# RFLNA.net
KiCad netlist of a schematic drawn in Altium Designer
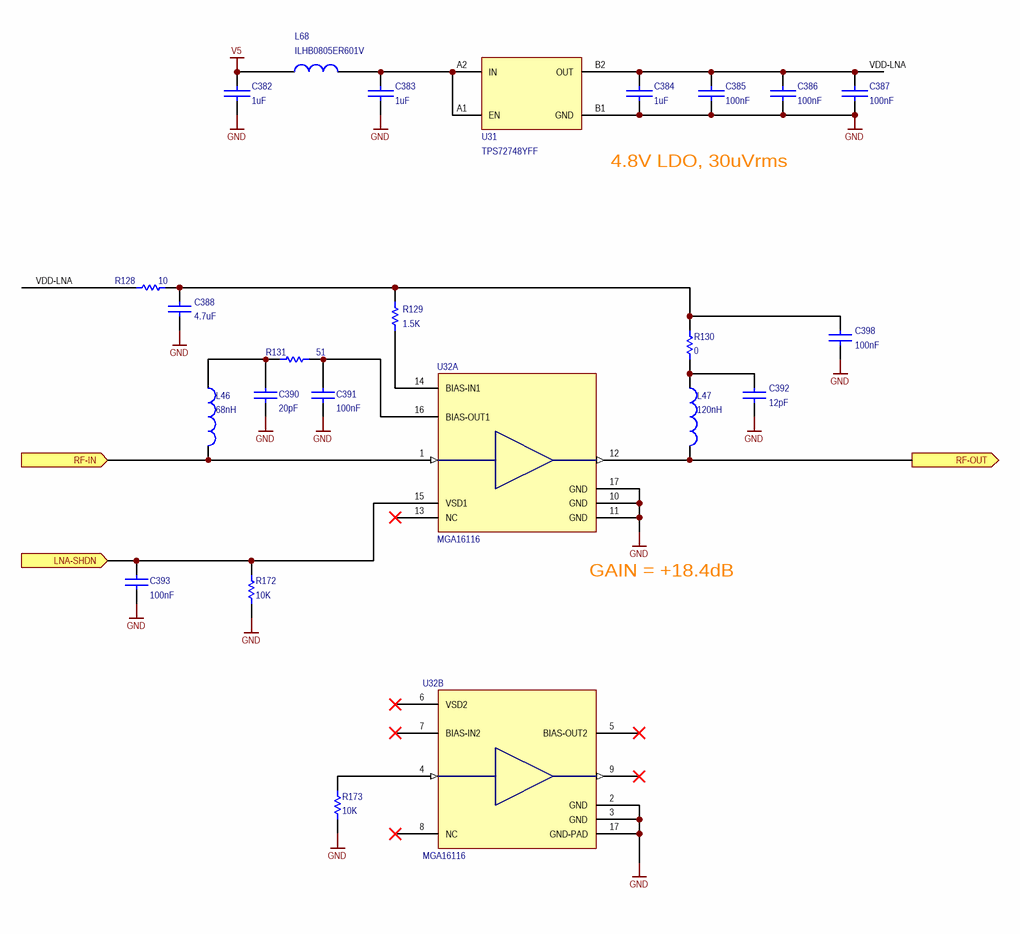
[diagram p0: RFLNA.SchDoc]

(export (version "E")
  (design (tool "Eeschema 10.0.6"))
  (components
    (comp (ref "C382")
      (value "1uF")
      (footprint "generic:0402")
      (description "Ceramic Capacitor 1uF ±10% 10V X5R 0402")
      (fields (field (name "MANUFACTURER") "Murata") (field (name "TOLERANCE") "±10%"))
      (libsource (lib "*") (part "CAP"))
    )
    (comp (ref "C383")
      (value "1uF")
      (footprint "generic:0402")
      (description "Ceramic Capacitor 1uF ±10% 10V X5R 0402")
      (fields (field (name "MANUFACTURER") "Murata") (field (name "TOLERANCE") "±10%"))
      (libsource (lib "*") (part "CAP"))
    )
    (comp (ref "C384")
      (value "1uF")
      (footprint "generic:0402")
      (description "Ceramic Capacitor 1uF ±10% 10V X5R 0402")
      (fields (field (name "MANUFACTURER") "Murata") (field (name "TOLERANCE") "±10%"))
      (libsource (lib "*") (part "CAP"))
    )
    (comp (ref "C385")
      (value "100nF")
      (footprint "generic:0402")
      (description "Ceramic Capacitor 100nF ±10% 16V X7R 0402")
      (fields (field (name "MANUFACTURER") "Murata") (field (name "VOLTAGE") "16V"))
      (libsource (lib "*") (part "CAP"))
    )
    (comp (ref "C386")
      (value "100nF")
      (footprint "generic:0402")
      (description "Ceramic Capacitor 100nF ±10% 16V X7R 0402")
      (fields (field (name "MANUFACTURER") "Murata") (field (name "VOLTAGE") "16V"))
      (libsource (lib "*") (part "CAP"))
    )
    (comp (ref "C387")
      (value "100nF")
      (footprint "generic:0402")
      (description "Ceramic Capacitor 100nF ±10% 16V X7R 0402")
      (fields (field (name "MANUFACTURER") "Murata") (field (name "VOLTAGE") "16V"))
      (libsource (lib "*") (part "CAP"))
    )
    (comp (ref "C388")
      (value "4.7uF")
      (footprint "generic:0603")
      (description "Ceramic Capacitor 4.7uF ±10% 25V X5R 0603")
      (fields (field (name "VOLTAGE") "25V") (field (name "MANUFACTURER") "Samsung"))
      (libsource (lib "Graviton") (part "CAP 0603"))
    )
    (comp (ref "C390")
      (value "20pF")
      (footprint "generic:0402")
      (description "Ceramic Capacitor 20pF ±1% 50V NP0 0402")
      (fields (field (name "VOLTAGE") "50V") (field (name "MANUFACTURER") "Kemet"))
      (libsource (lib "PopRock") (part "CAP 0402"))
    )
    (comp (ref "C391")
      (value "100nF")
      (footprint "generic:0402")
      (description "Ceramic Capacitor 100nF ±10% 16V X7R 0402")
      (fields (field (name "VOLTAGE") "16V") (field (name "MANUFACTURER") "Murata"))
      (libsource (lib "Graviton") (part "CAP 0402"))
    )
    (comp (ref "C392")
      (value "12pF")
      (footprint "generic:0402")
      (description "Ceramic Capacitor 12pF ±1% 50V NP0 0402")
      (fields (field (name "VOLTAGE") "50V") (field (name "MANUFACTURER") "Kemet"))
      (libsource (lib "Graviton") (part "CAP 0402"))
    )
    (comp (ref "C393")
      (value "100nF")
      (footprint "generic:0402")
      (description "Ceramic Capacitor 100nF ±10% 16V X7R 0402")
      (fields (field (name "VOLTAGE") "16V") (field (name "MANUFACTURER") "Murata"))
      (libsource (lib "Graviton") (part "CAP 0402"))
    )
    (comp (ref "C398")
      (value "100nF")
      (footprint "generic:0402")
      (description "Ceramic Capacitor 100nF ±10% 16V X7R 0402")
      (fields (field (name "VOLTAGE") "16V") (field (name "MANUFACTURER") "Murata"))
      (libsource (lib "Graviton") (part "CAP 0402"))
    )
    (comp (ref "L46")
      (value "68nH")
      (footprint "0402")
      (description "Inductor Wirewound 68nH ±5% 0402")
      (fields (field (name "MANUFACTURER") "Murata") (field (name "TOLERANCE") "±2%"))
      (libsource (lib "generic") (part "INDUCTOR"))
    )
    (comp (ref "L47")
      (value "120nH")
      (footprint "0402")
      (description "Inductor Wirewound 120nH ±5% 0402")
      (fields (field (name "MANUFACTURER") "Murata") (field (name "TOLERANCE") "±5%"))
      (libsource (lib "generic") (part "INDUCTOR"))
    )
    (comp (ref "L68")
      (value "ILHB0805ER601V")
      (footprint "0805")
      (description "Ferrite Bead 600-Ohm @ 100MHz 2A 0805")
      (fields (field (name "MANUFACTURER") "Vishay Dale") (field (name "TOLERANCE") "±25%"))
      (libsource (lib "*") (part "INDUCTANCE1"))
    )
    (comp (ref "R128")
      (value "10")
      (footprint "generic:0603")
      (description "Thick Film Resistor 10 ±1% 0603")
      (fields (field (name "MANUFACTURER") "Yageo") (field (name "TOLERANCE") "±1%"))
      (libsource (lib "Graviton") (part "RES 0603"))
    )
    (comp (ref "R129")
      (value "1.5K")
      (footprint "generic:0603")
      (description "Thick Film Resistor 1.5k ±1% 0603")
      (fields (field (name "MANUFACTURER") "Yageo") (field (name "TOLERANCE") "±1%"))
      (libsource (lib "Graviton") (part "RES 0603"))
    )
    (comp (ref "R130")
      (value "0")
      (footprint "generic:0603")
      (description "Thick Film Resistor Jumper 0603")
      (fields (field (name "MANUFACTURER") "Panasonic") (field (name "Comment") "ERJ-3GEY0R00V"))
      (libsource (lib "Graviton") (part "RES 0603"))
    )
    (comp (ref "R131")
      (value "51")
      (footprint "generic:0402")
      (description "Thick Film Resistor 51 ±1% 0402")
      (fields (field (name "MANUFACTURER") "Panasonic") (field (name "TOLERANCE") "±1%"))
      (libsource (lib "Graviton") (part "RES 0402"))
    )
    (comp (ref "R172")
      (value "10K")
      (footprint "generic:0402")
      (description "Thick Film 10k ±1% 0402")
      (fields (field (name "MANUFACTURER") "Panasonic") (field (name "TOLERANCE") "±1%"))
      (libsource (lib "Graviton") (part "RES 0402"))
    )
    (comp (ref "R173")
      (value "10K")
      (footprint "generic:0402")
      (description "Thick Film 10k ±1% 0402")
      (fields (field (name "MANUFACTURER") "Panasonic") (field (name "TOLERANCE") "±1%"))
      (libsource (lib "Graviton") (part "RES 0402"))
    )
    (comp (ref "U31")
      (value "TPS72748YFF")
      (footprint "DSBGA-4")
      (description "Ultralow Noise 30uVrms LDO, Fixed, 4.8V, 200mA")
      (fields
        (field (name "MANUFACTURER P/N") "TPS72748YFF")
        (field (name "MANUFACTURER") "Texas Instruments")
      )
      (libsource (lib "ti") (part "TPS72748YFF"))
    )
    (comp (ref "U32")
      (value "MGA16116")
      (footprint "QFN-16-AVAGO")
      (description "Dual Amplifier, Ultra-Low-Noise, 450-1450MHz")
      (fields (field (name "MANUFACTURER") "Avago"))
      (libsource (lib "avago") (part "MGA-16116"))
    )
  )
  (nets
    (net (code "1") (name "/LNA-SHDN") (class "Default")
      (node (ref "C393") (pin "2") (pinfunction "2_2") (pintype "passive"))
      (node (ref "R172") (pin "2") (pinfunction "2_2") (pintype "passive"))
      (node (ref "U32") (pin "15") (pinfunction "VSD1_15") (pintype "passive"))
    )
    (net (code "2") (name "/RF-IN") (class "Default")
      (node (ref "L46") (pin "2") (pinfunction "2_2") (pintype "passive"))
      (node (ref "U32") (pin "1") (pinfunction "RFIN1_1") (pintype "input"))
    )
    (net (code "3") (name "/RF-OUT") (class "Default")
      (node (ref "L47") (pin "2") (pinfunction "2_2") (pintype "passive"))
      (node (ref "U32") (pin "12") (pinfunction "RFOUT1_12") (pintype "output"))
    )
    (net (code "4") (name "/VDD-LNA") (class "Default")
      (node (ref "C384") (pin "2") (pinfunction "2_2") (pintype "passive"))
      (node (ref "C385") (pin "2") (pinfunction "2_2") (pintype "passive"))
      (node (ref "C386") (pin "2") (pinfunction "2_2") (pintype "passive"))
      (node (ref "C387") (pin "2") (pinfunction "2_2") (pintype "passive"))
      (node (ref "R128") (pin "1") (pinfunction "1_1") (pintype "passive"))
      (node (ref "U31") (pin "B2") (pinfunction "OUT_B2") (pintype "passive"))
    )
    (net (code "5") (name "GND") (class "Default")
      (node (ref "C382") (pin "1") (pinfunction "1_1") (pintype "passive"))
      (node (ref "C383") (pin "1") (pinfunction "1_1") (pintype "passive"))
      (node (ref "C384") (pin "1") (pinfunction "1_1") (pintype "passive"))
      (node (ref "C385") (pin "1") (pinfunction "1_1") (pintype "passive"))
      (node (ref "C386") (pin "1") (pinfunction "1_1") (pintype "passive"))
      (node (ref "C387") (pin "1") (pinfunction "1_1") (pintype "passive"))
      (node (ref "C388") (pin "1") (pinfunction "1_1") (pintype "passive"))
      (node (ref "C390") (pin "2") (pinfunction "2_2") (pintype "passive"))
      (node (ref "C391") (pin "1") (pinfunction "1_1") (pintype "passive"))
      (node (ref "C392") (pin "1") (pinfunction "1_1") (pintype "passive"))
      (node (ref "C393") (pin "1") (pinfunction "1_1") (pintype "passive"))
      (node (ref "C398") (pin "1") (pinfunction "1_1") (pintype "passive"))
      (node (ref "R172") (pin "1") (pinfunction "1_1") (pintype "passive"))
      (node (ref "R173") (pin "1") (pinfunction "1_1") (pintype "passive"))
      (node (ref "U31") (pin "B1") (pinfunction "GND_B1") (pintype "passive"))
      (node (ref "U32") (pin "10") (pinfunction "GND_10") (pintype "passive"))
      (node (ref "U32") (pin "11") (pinfunction "GND_11") (pintype "passive"))
      (node (ref "U32") (pin "17") (pinfunction "GND-PAD_17") (pintype "passive"))
      (node (ref "U32") (pin "2") (pinfunction "GND_2") (pintype "passive"))
      (node (ref "U32") (pin "3") (pinfunction "GND_3") (pintype "passive"))
    )
    (net (code "6") (name "Net-(C388-Pad2)") (class "Default")
      (node (ref "C388") (pin "2") (pinfunction "2_2") (pintype "passive"))
      (node (ref "C398") (pin "2") (pinfunction "2_2") (pintype "passive"))
      (node (ref "R128") (pin "2") (pinfunction "2_2") (pintype "passive"))
      (node (ref "R129") (pin "2") (pinfunction "2_2") (pintype "passive"))
      (node (ref "R130") (pin "2") (pinfunction "2_2") (pintype "passive"))
    )
    (net (code "7") (name "Net-(C390-Pad1)") (class "Default")
      (node (ref "C390") (pin "1") (pinfunction "1_1") (pintype "passive"))
      (node (ref "L46") (pin "1") (pinfunction "1_1") (pintype "passive"))
      (node (ref "R131") (pin "1") (pinfunction "1_1") (pintype "passive"))
    )
    (net (code "8") (name "Net-(C392-Pad2)") (class "Default")
      (node (ref "C392") (pin "2") (pinfunction "2_2") (pintype "passive"))
      (node (ref "L47") (pin "1") (pinfunction "1_1") (pintype "passive"))
      (node (ref "R130") (pin "1") (pinfunction "1_1") (pintype "passive"))
    )
    (net (code "9") (name "Net-(U31-EN)") (class "Default")
      (node (ref "C383") (pin "2") (pinfunction "2_2") (pintype "passive"))
      (node (ref "L68") (pin "1") (pinfunction "1_1") (pintype "passive"))
      (node (ref "U31") (pin "A1") (pinfunction "EN_A1") (pintype "passive"))
      (node (ref "U31") (pin "A2") (pinfunction "IN_A2") (pintype "passive"))
    )
    (net (code "10") (name "Net-(U32A-BIAS-IN1)") (class "Default")
      (node (ref "R129") (pin "1") (pinfunction "1_1") (pintype "passive"))
      (node (ref "U32") (pin "14") (pinfunction "BIAS-IN1_14") (pintype "passive"))
    )
    (net (code "11") (name "Net-(U32A-BIAS-OUT1)") (class "Default")
      (node (ref "C391") (pin "2") (pinfunction "2_2") (pintype "passive"))
      (node (ref "R131") (pin "2") (pinfunction "2_2") (pintype "passive"))
      (node (ref "U32") (pin "16") (pinfunction "BIAS-OUT1_16") (pintype "passive"))
    )
    (net (code "12") (name "Net-(U32B-RFIN2)") (class "Default")
      (node (ref "R173") (pin "2") (pinfunction "2_2") (pintype "passive"))
      (node (ref "U32") (pin "4") (pinfunction "RFIN2_4") (pintype "input"))
    )
    (net (code "13") (name "V5") (class "Default")
      (node (ref "C382") (pin "2") (pinfunction "2_2") (pintype "passive"))
      (node (ref "L68") (pin "2") (pinfunction "2_2") (pintype "passive"))
    )
    (net (code "14") (name "unconnected-(U32A-NC-Pad13)") (class "Default")
      (node (ref "U32") (pin "13") (pinfunction "NC_13") (pintype "passive+no_connect"))
    )
    (net (code "15") (name "unconnected-(U32B-BIAS-IN2-Pad7)") (class "Default")
      (node (ref "U32") (pin "7") (pinfunction "BIAS-IN2_7") (pintype "passive+no_connect"))
    )
    (net (code "16") (name "unconnected-(U32B-BIAS-OUT2-Pad5)") (class "Default")
      (node (ref "U32") (pin "5") (pinfunction "BIAS-OUT2_5") (pintype "passive+no_connect"))
    )
    (net (code "17") (name "unconnected-(U32B-NC-Pad8)") (class "Default")
      (node (ref "U32") (pin "8") (pinfunction "NC_8") (pintype "passive+no_connect"))
    )
    (net (code "18") (name "unconnected-(U32B-RFOUT2-Pad9)") (class "Default")
      (node (ref "U32") (pin "9") (pinfunction "RFOUT2_9") (pintype "output+no_connect"))
    )
    (net (code "19") (name "unconnected-(U32B-VSD2-Pad6)") (class "Default")
      (node (ref "U32") (pin "6") (pinfunction "VSD2_6") (pintype "passive+no_connect"))
    )
  )
)
